# Sheet1.net
KiCad netlist of a schematic drawn in Altium Designer
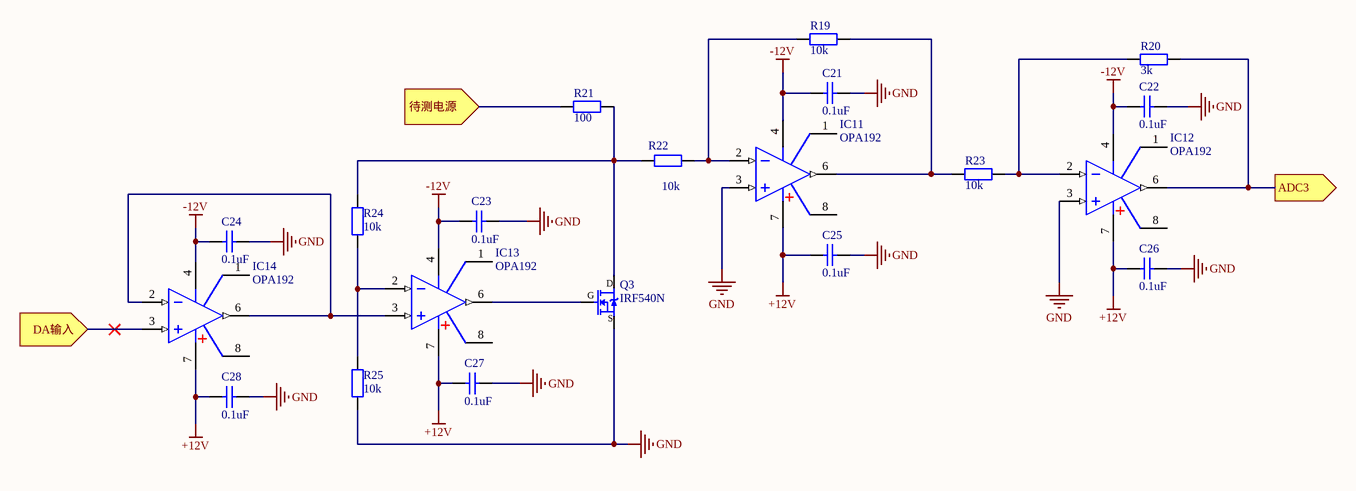
[diagram p0: Sheet1.SchDoc]

(export (version "E")
  (design (tool "Eeschema 10.0.6"))
  (components
    (comp (ref "C21")
      (value "0.1uF")
      (footprint "瓷片电容")
      (description "直插电容")
      (fields (field (name "VOLTAGE") "63V") (field (name "PUBLISHER") "Altium Limited"))
      (libsource (lib "My_Intlib") (part "Cap_DIP"))
    )
    (comp (ref "C22")
      (value "0.1uF")
      (footprint "瓷片电容")
      (description "直插电容")
      (fields (field (name "VOLTAGE") "63V") (field (name "PUBLISHER") "Altium Limited"))
      (libsource (lib "My_Intlib") (part "Cap_DIP"))
    )
    (comp (ref "C23")
      (value "0.1uF")
      (footprint "瓷片电容")
      (description "直插电容")
      (fields (field (name "VOLTAGE") "63V") (field (name "PUBLISHER") "Altium Limited"))
      (libsource (lib "My_Intlib") (part "Cap_DIP"))
    )
    (comp (ref "C24")
      (value "0.1uF")
      (footprint "瓷片电容")
      (description "直插电容")
      (fields (field (name "VOLTAGE") "63V") (field (name "PUBLISHER") "Altium Limited"))
      (libsource (lib "My_Intlib") (part "Cap_DIP"))
    )
    (comp (ref "C25")
      (value "0.1uF")
      (footprint "瓷片电容")
      (description "直插电容")
      (fields (field (name "VOLTAGE") "63V") (field (name "PUBLISHER") "Altium Limited"))
      (libsource (lib "My_Intlib") (part "Cap_DIP"))
    )
    (comp (ref "C26")
      (value "0.1uF")
      (footprint "瓷片电容")
      (description "直插电容")
      (fields (field (name "VOLTAGE") "63V") (field (name "PUBLISHER") "Altium Limited"))
      (libsource (lib "My_Intlib") (part "Cap_DIP"))
    )
    (comp (ref "C27")
      (value "0.1uF")
      (footprint "瓷片电容")
      (description "直插电容")
      (fields (field (name "VOLTAGE") "63V") (field (name "PUBLISHER") "Altium Limited"))
      (libsource (lib "My_Intlib") (part "Cap_DIP"))
    )
    (comp (ref "C28")
      (value "0.1uF")
      (footprint "瓷片电容")
      (description "直插电容")
      (fields (field (name "VOLTAGE") "63V") (field (name "PUBLISHER") "Altium Limited"))
      (libsource (lib "My_Intlib") (part "Cap_DIP"))
    )
    (comp (ref "IC11")
      (value "OPA192")
      (footprint "SOP8_N")
      (description "High-Voltage, Rail-to-Rail Input/Output, 5µV, 0.2µV/˚C, Precision Operational Amplifier")
      (fields (field (name "版权归属") "源创客"))
      (libsource (lib "My_Intlib") (part "OPA192"))
    )
    (comp (ref "IC12")
      (value "OPA192")
      (footprint "SOP8_N")
      (description "High-Voltage, Rail-to-Rail Input/Output, 5µV, 0.2µV/˚C, Precision Operational Amplifier")
      (fields (field (name "版权归属") "源创客"))
      (libsource (lib "My_Intlib") (part "OPA192"))
    )
    (comp (ref "IC13")
      (value "OPA192")
      (footprint "SOP8_N")
      (description "High-Voltage, Rail-to-Rail Input/Output, 5µV, 0.2µV/˚C, Precision Operational Amplifier")
      (fields (field (name "版权归属") "源创客"))
      (libsource (lib "My_Intlib") (part "OPA192"))
    )
    (comp (ref "IC14")
      (value "OPA192")
      (footprint "SOP8_N")
      (description "High-Voltage, Rail-to-Rail Input/Output, 5µV, 0.2µV/˚C, Precision Operational Amplifier")
      (fields (field (name "版权归属") "源创客"))
      (libsource (lib "My_Intlib") (part "OPA192"))
    )
    (comp (ref "Q3")
      (value "IRF540N")
      (footprint "TO263-3B")
      (description "N沟场 100V/22A")
      (fields (field (name "版权归属") "源创客"))
      (libsource (lib "My_Intlib") (part "IRF540N"))
    )
    (comp (ref "R19")
      (value "10k")
      (footprint "RS 1/4W")
      (description "直插电阻")
      (libsource (lib "My_Intlib") (part "Res_DIP"))
    )
    (comp (ref "R20")
      (value "3k")
      (footprint "RS 1/4W")
      (description "直插电阻")
      (libsource (lib "My_Intlib") (part "Res_DIP"))
    )
    (comp (ref "R21")
      (value "100")
      (footprint "RS 1/4W")
      (description "直插电阻")
      (libsource (lib "") (part "Res_DIP_2"))
    )
    (comp (ref "R22")
      (value "10k")
      (footprint "RS 1/4W")
      (description "直插电阻")
      (libsource (lib "My_Intlib") (part "Res_DIP"))
    )
    (comp (ref "R23")
      (value "10k")
      (footprint "RS 1/4W")
      (description "直插电阻")
      (libsource (lib "My_Intlib") (part "Res_DIP"))
    )
    (comp (ref "R24")
      (value "10k")
      (footprint "RS 1/4W")
      (description "直插电阻")
      (libsource (lib "") (part "Res_DIP_1"))
    )
    (comp (ref "R25")
      (value "10k")
      (footprint "RS 1/4W")
      (description "直插电阻")
      (libsource (lib "") (part "Res_DIP_1"))
    )
  )
  (nets
    (net (code "1") (name "+12V") (class "Default")
      (node (ref "C25") (pin "1") (pinfunction "1_1") (pintype "passive"))
      (node (ref "C26") (pin "1") (pinfunction "1_1") (pintype "passive"))
      (node (ref "C27") (pin "1") (pinfunction "1_1") (pintype "passive"))
      (node (ref "C28") (pin "1") (pinfunction "1_1") (pintype "passive"))
      (node (ref "IC11") (pin "7") (pinfunction "V+_7") (pintype "power_in"))
      (node (ref "IC12") (pin "7") (pinfunction "V+_7") (pintype "power_in"))
      (node (ref "IC13") (pin "7") (pinfunction "V+_7") (pintype "power_in"))
      (node (ref "IC14") (pin "7") (pinfunction "V+_7") (pintype "power_in"))
    )
    (net (code "2") (name "-12V") (class "Default")
      (node (ref "C21") (pin "1") (pinfunction "1_1") (pintype "passive"))
      (node (ref "C22") (pin "1") (pinfunction "1_1") (pintype "passive"))
      (node (ref "C23") (pin "1") (pinfunction "1_1") (pintype "passive"))
      (node (ref "C24") (pin "1") (pinfunction "1_1") (pintype "passive"))
      (node (ref "IC11") (pin "4") (pinfunction "V-_4") (pintype "power_in"))
      (node (ref "IC12") (pin "4") (pinfunction "V-_4") (pintype "power_in"))
      (node (ref "IC13") (pin "4") (pinfunction "V-_4") (pintype "power_in"))
      (node (ref "IC14") (pin "4") (pinfunction "V-_4") (pintype "power_in"))
    )
    (net (code "3") (name "/ADC3") (class "Default")
      (node (ref "IC12") (pin "6") (pinfunction "OUT_6") (pintype "output"))
      (node (ref "R20") (pin "2") (pinfunction "2_2") (pintype "passive"))
    )
    (net (code "4") (name "/DA输入") (class "Default")
      (node (ref "IC14") (pin "3") (pinfunction "IN+_3") (pintype "input"))
    )
    (net (code "5") (name "/待测电源") (class "Default")
      (node (ref "R21") (pin "2") (pinfunction "2_2") (pintype "passive"))
    )
    (net (code "6") (name "GND") (class "Default")
      (node (ref "C21") (pin "2") (pinfunction "2_2") (pintype "passive"))
      (node (ref "C22") (pin "2") (pinfunction "2_2") (pintype "passive"))
      (node (ref "C23") (pin "2") (pinfunction "2_2") (pintype "passive"))
      (node (ref "C24") (pin "2") (pinfunction "2_2") (pintype "passive"))
      (node (ref "C25") (pin "2") (pinfunction "2_2") (pintype "passive"))
      (node (ref "C26") (pin "2") (pinfunction "2_2") (pintype "passive"))
      (node (ref "C27") (pin "2") (pinfunction "2_2") (pintype "passive"))
      (node (ref "C28") (pin "2") (pinfunction "2_2") (pintype "passive"))
      (node (ref "IC11") (pin "3") (pinfunction "IN+_3") (pintype "input"))
      (node (ref "IC12") (pin "3") (pinfunction "IN+_3") (pintype "input"))
      (node (ref "Q3") (pin "3") (pinfunction "D_3") (pintype "passive"))
      (node (ref "R25") (pin "1") (pinfunction "1_1") (pintype "passive"))
    )
    (net (code "7") (name "Net-(IC11-IN-)") (class "Default")
      (node (ref "IC11") (pin "2") (pinfunction "IN-_2") (pintype "input"))
      (node (ref "R19") (pin "1") (pinfunction "1_1") (pintype "passive"))
      (node (ref "R22") (pin "2") (pinfunction "2_2") (pintype "passive"))
    )
    (net (code "8") (name "Net-(IC11-OUT)") (class "Default")
      (node (ref "IC11") (pin "6") (pinfunction "OUT_6") (pintype "output"))
      (node (ref "R19") (pin "2") (pinfunction "2_2") (pintype "passive"))
      (node (ref "R23") (pin "1") (pinfunction "1_1") (pintype "passive"))
    )
    (net (code "9") (name "Net-(IC12-IN-)") (class "Default")
      (node (ref "IC12") (pin "2") (pinfunction "IN-_2") (pintype "input"))
      (node (ref "R20") (pin "1") (pinfunction "1_1") (pintype "passive"))
      (node (ref "R23") (pin "2") (pinfunction "2_2") (pintype "passive"))
    )
    (net (code "10") (name "Net-(IC13-IN+)") (class "Default")
      (node (ref "IC13") (pin "3") (pinfunction "IN+_3") (pintype "input"))
      (node (ref "IC14") (pin "2") (pinfunction "IN-_2") (pintype "input"))
      (node (ref "IC14") (pin "6") (pinfunction "OUT_6") (pintype "output"))
    )
    (net (code "11") (name "Net-(IC13-IN-)") (class "Default")
      (node (ref "IC13") (pin "2") (pinfunction "IN-_2") (pintype "input"))
      (node (ref "R24") (pin "1") (pinfunction "1_1") (pintype "passive"))
      (node (ref "R25") (pin "2") (pinfunction "2_2") (pintype "passive"))
    )
    (net (code "12") (name "Net-(IC13-OUT)") (class "Default")
      (node (ref "IC13") (pin "6") (pinfunction "OUT_6") (pintype "output"))
      (node (ref "Q3") (pin "1") (pinfunction "G_1") (pintype "passive"))
    )
    (net (code "13") (name "Net-(Q3-S)") (class "Default")
      (node (ref "Q3") (pin "2") (pinfunction "S_2") (pintype "passive"))
      (node (ref "R21") (pin "1") (pinfunction "1_1") (pintype "passive"))
      (node (ref "R22") (pin "1") (pinfunction "1_1") (pintype "passive"))
      (node (ref "R24") (pin "2") (pinfunction "2_2") (pintype "passive"))
    )
    (net (code "14") (name "unconnected-(IC11-Pad1)") (class "Default")
      (node (ref "IC11") (pin "1") (pinfunction "1_1") (pintype "passive"))
    )
    (net (code "15") (name "unconnected-(IC11-Pad8)") (class "Default")
      (node (ref "IC11") (pin "8") (pinfunction "8_8") (pintype "passive"))
    )
    (net (code "16") (name "unconnected-(IC12-Pad1)") (class "Default")
      (node (ref "IC12") (pin "1") (pinfunction "1_1") (pintype "passive"))
    )
    (net (code "17") (name "unconnected-(IC12-Pad8)") (class "Default")
      (node (ref "IC12") (pin "8") (pinfunction "8_8") (pintype "passive"))
    )
    (net (code "18") (name "unconnected-(IC13-Pad1)") (class "Default")
      (node (ref "IC13") (pin "1") (pinfunction "1_1") (pintype "passive"))
    )
    (net (code "19") (name "unconnected-(IC13-Pad8)") (class "Default")
      (node (ref "IC13") (pin "8") (pinfunction "8_8") (pintype "passive"))
    )
    (net (code "20") (name "unconnected-(IC14-Pad1)") (class "Default")
      (node (ref "IC14") (pin "1") (pinfunction "1_1") (pintype "passive"))
    )
    (net (code "21") (name "unconnected-(IC14-Pad8)") (class "Default")
      (node (ref "IC14") (pin "8") (pinfunction "8_8") (pintype "passive"))
    )
  )
)
